# v001.net
KiCad netlist of a schematic drawn in EAGLE
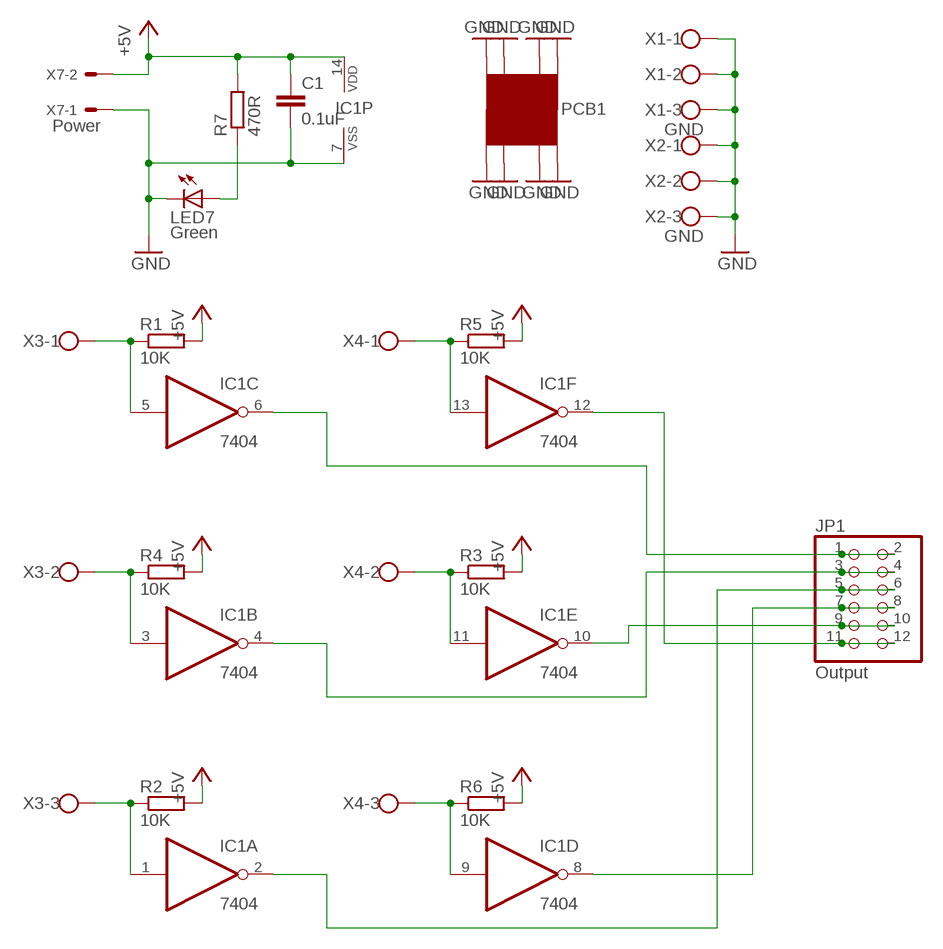
[diagram p0: schematic, sheet 1]

(export (version "E")
  (design (tool "Eeschema 10.0.6"))
  (components
    (comp (ref "C1")
      (value "0.1uF")
      (footprint "eagle-import:C050-024X044")
      (libsource (lib "eagle-import") (part "C-EU050-024X044"))
    )
    (comp (ref "IC1")
      (value "7404")
      (footprint "eagle-import:DIL14")
      (libsource (lib "eagle-import") (part "4584N"))
    )
    (comp (ref "JP1")
      (value "Output")
      (footprint "eagle-import:2X06")
      (libsource (lib "eagle-import") (part "PINHD-2X6"))
    )
    (comp (ref "LED7")
      (value "Green")
      (footprint "eagle-import:LED3MM")
      (libsource (lib "eagle-import") (part "LED3MM"))
    )
    (comp (ref "PCB1")
      (value "PCB05X05")
      (footprint "eagle-import:PCB_05X05")
      (libsource (lib "eagle-import") (part "PCB05X05"))
    )
    (comp (ref "R1")
      (value "10K")
      (footprint "eagle-import:0207_2V")
      (libsource (lib "eagle-import") (part "R-EU_0207/2V"))
    )
    (comp (ref "R2")
      (value "10K")
      (footprint "eagle-import:0207_2V")
      (libsource (lib "eagle-import") (part "R-EU_0207/2V"))
    )
    (comp (ref "R3")
      (value "10K")
      (footprint "eagle-import:0207_2V")
      (libsource (lib "eagle-import") (part "R-EU_0207/2V"))
    )
    (comp (ref "R4")
      (value "10K")
      (footprint "eagle-import:0207_2V")
      (libsource (lib "eagle-import") (part "R-EU_0207/2V"))
    )
    (comp (ref "R5")
      (value "10K")
      (footprint "eagle-import:0207_2V")
      (libsource (lib "eagle-import") (part "R-EU_0207/2V"))
    )
    (comp (ref "R6")
      (value "10K")
      (footprint "eagle-import:0207_2V")
      (libsource (lib "eagle-import") (part "R-EU_0207/2V"))
    )
    (comp (ref "R7")
      (value "470R")
      (footprint "eagle-import:0207_2V")
      (libsource (lib "eagle-import") (part "R-EU_0207/2V"))
    )
    (comp (ref "X1")
      (value "GND")
      (footprint "eagle-import:W237-103")
      (fields (field (name "MPN") "237-103"))
      (libsource (lib "eagle-import") (part "W237-103"))
    )
    (comp (ref "X2")
      (value "GND")
      (footprint "eagle-import:W237-103")
      (fields (field (name "MPN") "237-103"))
      (libsource (lib "eagle-import") (part "W237-103"))
    )
    (comp (ref "X3")
      (value "W237-103")
      (footprint "eagle-import:W237-103")
      (fields (field (name "MPN") "237-103"))
      (libsource (lib "eagle-import") (part "W237-103"))
    )
    (comp (ref "X4")
      (value "W237-103")
      (footprint "eagle-import:W237-103")
      (fields (field (name "MPN") "237-103"))
      (libsource (lib "eagle-import") (part "W237-103"))
    )
    (comp (ref "X7")
      (value "Power")
      (footprint "eagle-import:6410-02")
      (libsource (lib "eagle-import") (part "22-?-0227-2021"))
    )
  )
  (nets
    (net (code "1") (name "+5V") (class "Default")
      (node (ref "C1") (pin "1") (pinfunction "1_1") (pintype "passive"))
      (node (ref "IC1") (pin "14") (pinfunction "VDD_14") (pintype "power_in"))
      (node (ref "R1") (pin "2") (pinfunction "2_2") (pintype "passive"))
      (node (ref "R2") (pin "2") (pinfunction "2_2") (pintype "passive"))
      (node (ref "R3") (pin "2") (pinfunction "2_2") (pintype "passive"))
      (node (ref "R4") (pin "2") (pinfunction "2_2") (pintype "passive"))
      (node (ref "R5") (pin "2") (pinfunction "2_2") (pintype "passive"))
      (node (ref "R6") (pin "2") (pinfunction "2_2") (pintype "passive"))
      (node (ref "R7") (pin "2") (pinfunction "2_2") (pintype "passive"))
      (node (ref "X7") (pin "2") (pinfunction "S_2") (pintype "passive"))
    )
    (net (code "2") (name "GND") (class "Default")
      (node (ref "C1") (pin "2") (pinfunction "2_2") (pintype "passive"))
      (node (ref "IC1") (pin "7") (pinfunction "VSS_7") (pintype "power_in"))
      (node (ref "LED7") (pin "K") (pinfunction "C_K") (pintype "passive"))
      (node (ref "PCB1") (pin "GND@1") (pinfunction "GND_GND@1") (pintype "bidirectional"))
      (node (ref "PCB1") (pin "GND@2") (pinfunction "GND_GND@2") (pintype "bidirectional"))
      (node (ref "PCB1") (pin "GND@3") (pinfunction "GND_GND@3") (pintype "bidirectional"))
      (node (ref "PCB1") (pin "GND@4") (pinfunction "GND_GND@4") (pintype "bidirectional"))
      (node (ref "PCB1") (pin "GND@5") (pinfunction "GND_GND@5") (pintype "bidirectional"))
      (node (ref "PCB1") (pin "GND@6") (pinfunction "GND_GND@6") (pintype "bidirectional"))
      (node (ref "PCB1") (pin "GND@7") (pinfunction "GND_GND@7") (pintype "bidirectional"))
      (node (ref "PCB1") (pin "GND@8") (pinfunction "GND_GND@8") (pintype "bidirectional"))
      (node (ref "X1") (pin "1") (pinfunction "KL_1") (pintype "passive"))
      (node (ref "X1") (pin "2") (pinfunction "KL_2") (pintype "passive"))
      (node (ref "X1") (pin "3") (pinfunction "KL_3") (pintype "passive"))
      (node (ref "X2") (pin "1") (pinfunction "KL_1") (pintype "passive"))
      (node (ref "X2") (pin "2") (pinfunction "KL_2") (pintype "passive"))
      (node (ref "X2") (pin "3") (pinfunction "KL_3") (pintype "passive"))
      (node (ref "X7") (pin "1") (pinfunction "S_1") (pintype "passive"))
    )
    (net (code "3") (name "Net-(IC1A-I)") (class "Default")
      (node (ref "IC1") (pin "1") (pinfunction "I_1") (pintype "input"))
      (node (ref "R2") (pin "1") (pinfunction "1_1") (pintype "passive"))
      (node (ref "X3") (pin "3") (pinfunction "KL_3") (pintype "passive"))
    )
    (net (code "4") (name "Net-(IC1A-O)") (class "Default")
      (node (ref "IC1") (pin "2") (pinfunction "O_2") (pintype "output"))
      (node (ref "JP1") (pin "5") (pinfunction "5_5") (pintype "passive"))
      (node (ref "JP1") (pin "6") (pinfunction "6_6") (pintype "passive"))
    )
    (net (code "5") (name "Net-(IC1B-I)") (class "Default")
      (node (ref "IC1") (pin "3") (pinfunction "I_3") (pintype "input"))
      (node (ref "R4") (pin "1") (pinfunction "1_1") (pintype "passive"))
      (node (ref "X3") (pin "2") (pinfunction "KL_2") (pintype "passive"))
    )
    (net (code "6") (name "Net-(IC1B-O)") (class "Default")
      (node (ref "IC1") (pin "4") (pinfunction "O_4") (pintype "output"))
      (node (ref "JP1") (pin "3") (pinfunction "3_3") (pintype "passive"))
      (node (ref "JP1") (pin "4") (pinfunction "4_4") (pintype "passive"))
    )
    (net (code "7") (name "Net-(IC1C-I)") (class "Default")
      (node (ref "IC1") (pin "5") (pinfunction "I_5") (pintype "input"))
      (node (ref "R1") (pin "1") (pinfunction "1_1") (pintype "passive"))
      (node (ref "X3") (pin "1") (pinfunction "KL_1") (pintype "passive"))
    )
    (net (code "8") (name "Net-(IC1C-O)") (class "Default")
      (node (ref "IC1") (pin "6") (pinfunction "O_6") (pintype "output"))
      (node (ref "JP1") (pin "1") (pinfunction "1_1") (pintype "passive"))
      (node (ref "JP1") (pin "2") (pinfunction "2_2") (pintype "passive"))
    )
    (net (code "9") (name "Net-(IC1D-I)") (class "Default")
      (node (ref "IC1") (pin "9") (pinfunction "I_9") (pintype "input"))
      (node (ref "R6") (pin "1") (pinfunction "1_1") (pintype "passive"))
      (node (ref "X4") (pin "3") (pinfunction "KL_3") (pintype "passive"))
    )
    (net (code "10") (name "Net-(IC1D-O)") (class "Default")
      (node (ref "IC1") (pin "8") (pinfunction "O_8") (pintype "output"))
      (node (ref "JP1") (pin "7") (pinfunction "7_7") (pintype "passive"))
      (node (ref "JP1") (pin "8") (pinfunction "8_8") (pintype "passive"))
    )
    (net (code "11") (name "Net-(IC1E-I)") (class "Default")
      (node (ref "IC1") (pin "11") (pinfunction "I_11") (pintype "input"))
      (node (ref "R3") (pin "1") (pinfunction "1_1") (pintype "passive"))
      (node (ref "X4") (pin "2") (pinfunction "KL_2") (pintype "passive"))
    )
    (net (code "12") (name "Net-(IC1E-O)") (class "Default")
      (node (ref "IC1") (pin "10") (pinfunction "O_10") (pintype "output"))
      (node (ref "JP1") (pin "10") (pinfunction "10_10") (pintype "passive"))
      (node (ref "JP1") (pin "9") (pinfunction "9_9") (pintype "passive"))
    )
    (net (code "13") (name "Net-(IC1F-I)") (class "Default")
      (node (ref "IC1") (pin "13") (pinfunction "I_13") (pintype "input"))
      (node (ref "R5") (pin "1") (pinfunction "1_1") (pintype "passive"))
      (node (ref "X4") (pin "1") (pinfunction "KL_1") (pintype "passive"))
    )
    (net (code "14") (name "Net-(IC1F-O)") (class "Default")
      (node (ref "IC1") (pin "12") (pinfunction "O_12") (pintype "output"))
      (node (ref "JP1") (pin "11") (pinfunction "11_11") (pintype "passive"))
      (node (ref "JP1") (pin "12") (pinfunction "12_12") (pintype "passive"))
    )
    (net (code "15") (name "Net-(LED7-PadA)") (class "Default")
      (node (ref "LED7") (pin "A") (pinfunction "A_A") (pintype "passive"))
      (node (ref "R7") (pin "1") (pinfunction "1_1") (pintype "passive"))
    )
  )
)
